# PWM_OUTS.net
KiCad netlist of a schematic drawn in Altium Designer
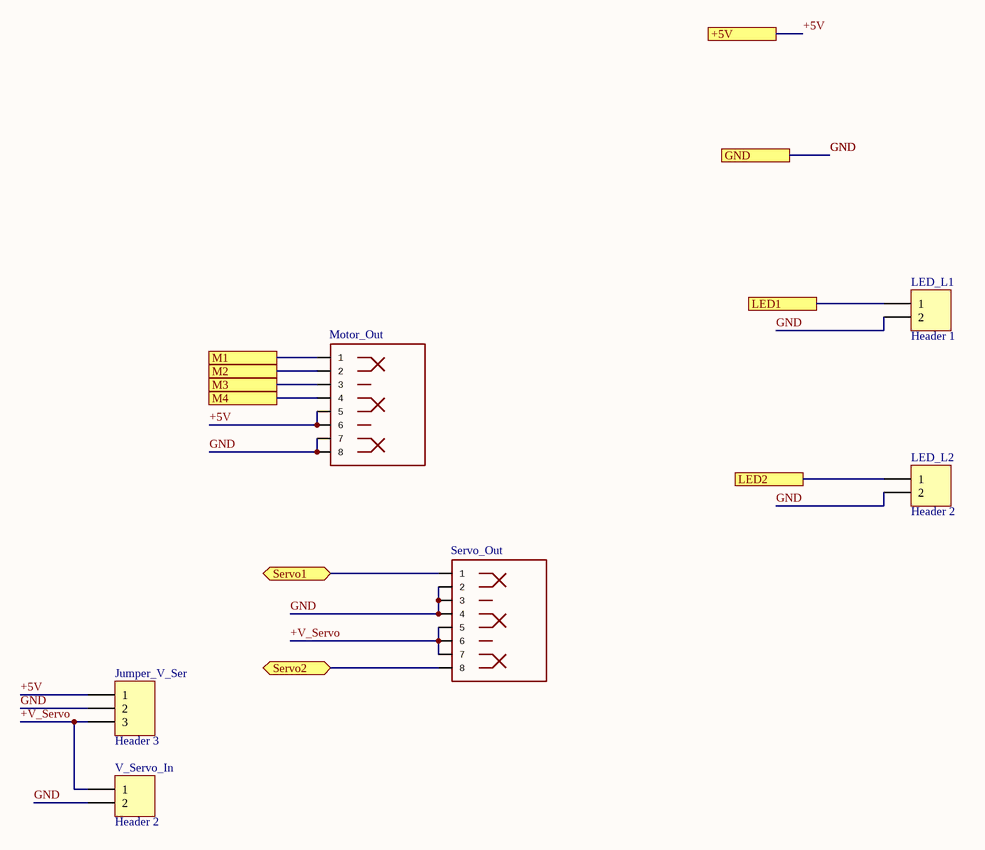
[diagram p0: PWM_OUTS.SchDoc]

(export (version "E")
  (design (tool "Eeschema 10.0.6"))
  (components
    (comp (ref "Jumper_V_Ser")
      (value "Header 3")
      (footprint "HDR1X3")
      (description "Header, 3-Pin")
      (fields (field (name "PUBLISHER") "Altium Limited"))
      (libsource (lib "Miscellaneous Connectors") (part "Header 3"))
    )
    (comp (ref "LED_L1")
      (value "Header 1")
      (footprint "HDR1X2")
      (description "Header, 2-Pin")
      (fields (field (name "PUBLISHER") "Altium Limited"))
      (libsource (lib "Miscellaneous Connectors") (part "Header 2"))
    )
    (comp (ref "LED_L2")
      (value "Header 2")
      (footprint "HDR1X2")
      (description "Header, 2-Pin")
      (fields (field (name "PUBLISHER") "Altium Limited"))
      (libsource (lib "Miscellaneous Connectors") (part "Header 2"))
    )
    (comp (ref "Motor_Out")
      (value "~")
      (footprint "RJ45-8")
      (libsource (lib "SparkFun-Connectors") (part "RJ45-8PTH"))
    )
    (comp (ref "Servo_Out")
      (value "~")
      (footprint "RJ45-8")
      (libsource (lib "SparkFun-Connectors") (part "RJ45-8PTH"))
    )
    (comp (ref "V_Servo_In")
      (value "Header 2")
      (footprint "HDR1X2")
      (description "Header, 2-Pin")
      (fields (field (name "PUBLISHER") "Altium Limited"))
      (libsource (lib "Miscellaneous Connectors") (part "Header 2"))
    )
  )
  (nets
    (net (code "1") (name "/+5V") (class "Default")
      (node (ref "Jumper_V_Ser") (pin "1") (pinfunction "1_1") (pintype "passive"))
      (node (ref "Motor_Out") (pin "5") (pinfunction "5_5") (pintype "passive"))
      (node (ref "Motor_Out") (pin "6") (pinfunction "6_6") (pintype "passive"))
    )
    (net (code "2") (name "/+V_Servo") (class "Default")
      (node (ref "Jumper_V_Ser") (pin "3") (pinfunction "3_3") (pintype "passive"))
      (node (ref "Servo_Out") (pin "5") (pinfunction "5_5") (pintype "passive"))
      (node (ref "Servo_Out") (pin "6") (pinfunction "6_6") (pintype "passive"))
      (node (ref "Servo_Out") (pin "7") (pinfunction "7_7") (pintype "passive"))
      (node (ref "V_Servo_In") (pin "1") (pinfunction "1_1") (pintype "passive"))
    )
    (net (code "3") (name "/GND") (class "Default")
      (node (ref "Jumper_V_Ser") (pin "2") (pinfunction "2_2") (pintype "passive"))
      (node (ref "LED_L1") (pin "2") (pinfunction "2_2") (pintype "passive"))
      (node (ref "LED_L2") (pin "2") (pinfunction "2_2") (pintype "passive"))
      (node (ref "Motor_Out") (pin "7") (pinfunction "7_7") (pintype "passive"))
      (node (ref "Motor_Out") (pin "8") (pinfunction "8_8") (pintype "passive"))
      (node (ref "Servo_Out") (pin "2") (pinfunction "2_2") (pintype "passive"))
      (node (ref "Servo_Out") (pin "3") (pinfunction "3_3") (pintype "passive"))
      (node (ref "Servo_Out") (pin "4") (pinfunction "4_4") (pintype "passive"))
      (node (ref "V_Servo_In") (pin "2") (pinfunction "2_2") (pintype "passive"))
    )
    (net (code "4") (name "/LED1") (class "Default")
      (node (ref "LED_L1") (pin "1") (pinfunction "1_1") (pintype "passive"))
    )
    (net (code "5") (name "/LED2") (class "Default")
      (node (ref "LED_L2") (pin "1") (pinfunction "1_1") (pintype "passive"))
    )
    (net (code "6") (name "/M1") (class "Default")
      (node (ref "Motor_Out") (pin "1") (pinfunction "1_1") (pintype "passive"))
    )
    (net (code "7") (name "/M2") (class "Default")
      (node (ref "Motor_Out") (pin "2") (pinfunction "2_2") (pintype "passive"))
    )
    (net (code "8") (name "/M3") (class "Default")
      (node (ref "Motor_Out") (pin "3") (pinfunction "3_3") (pintype "passive"))
    )
    (net (code "9") (name "/M4") (class "Default")
      (node (ref "Motor_Out") (pin "4") (pinfunction "4_4") (pintype "passive"))
    )
    (net (code "10") (name "/Servo1") (class "Default")
      (node (ref "Servo_Out") (pin "1") (pinfunction "1_1") (pintype "passive"))
    )
    (net (code "11") (name "/Servo2") (class "Default")
      (node (ref "Servo_Out") (pin "8") (pinfunction "8_8") (pintype "passive"))
    )
  )
)
